# SD2IEC_TicTac.net
KiCad netlist of a schematic drawn in EAGLE
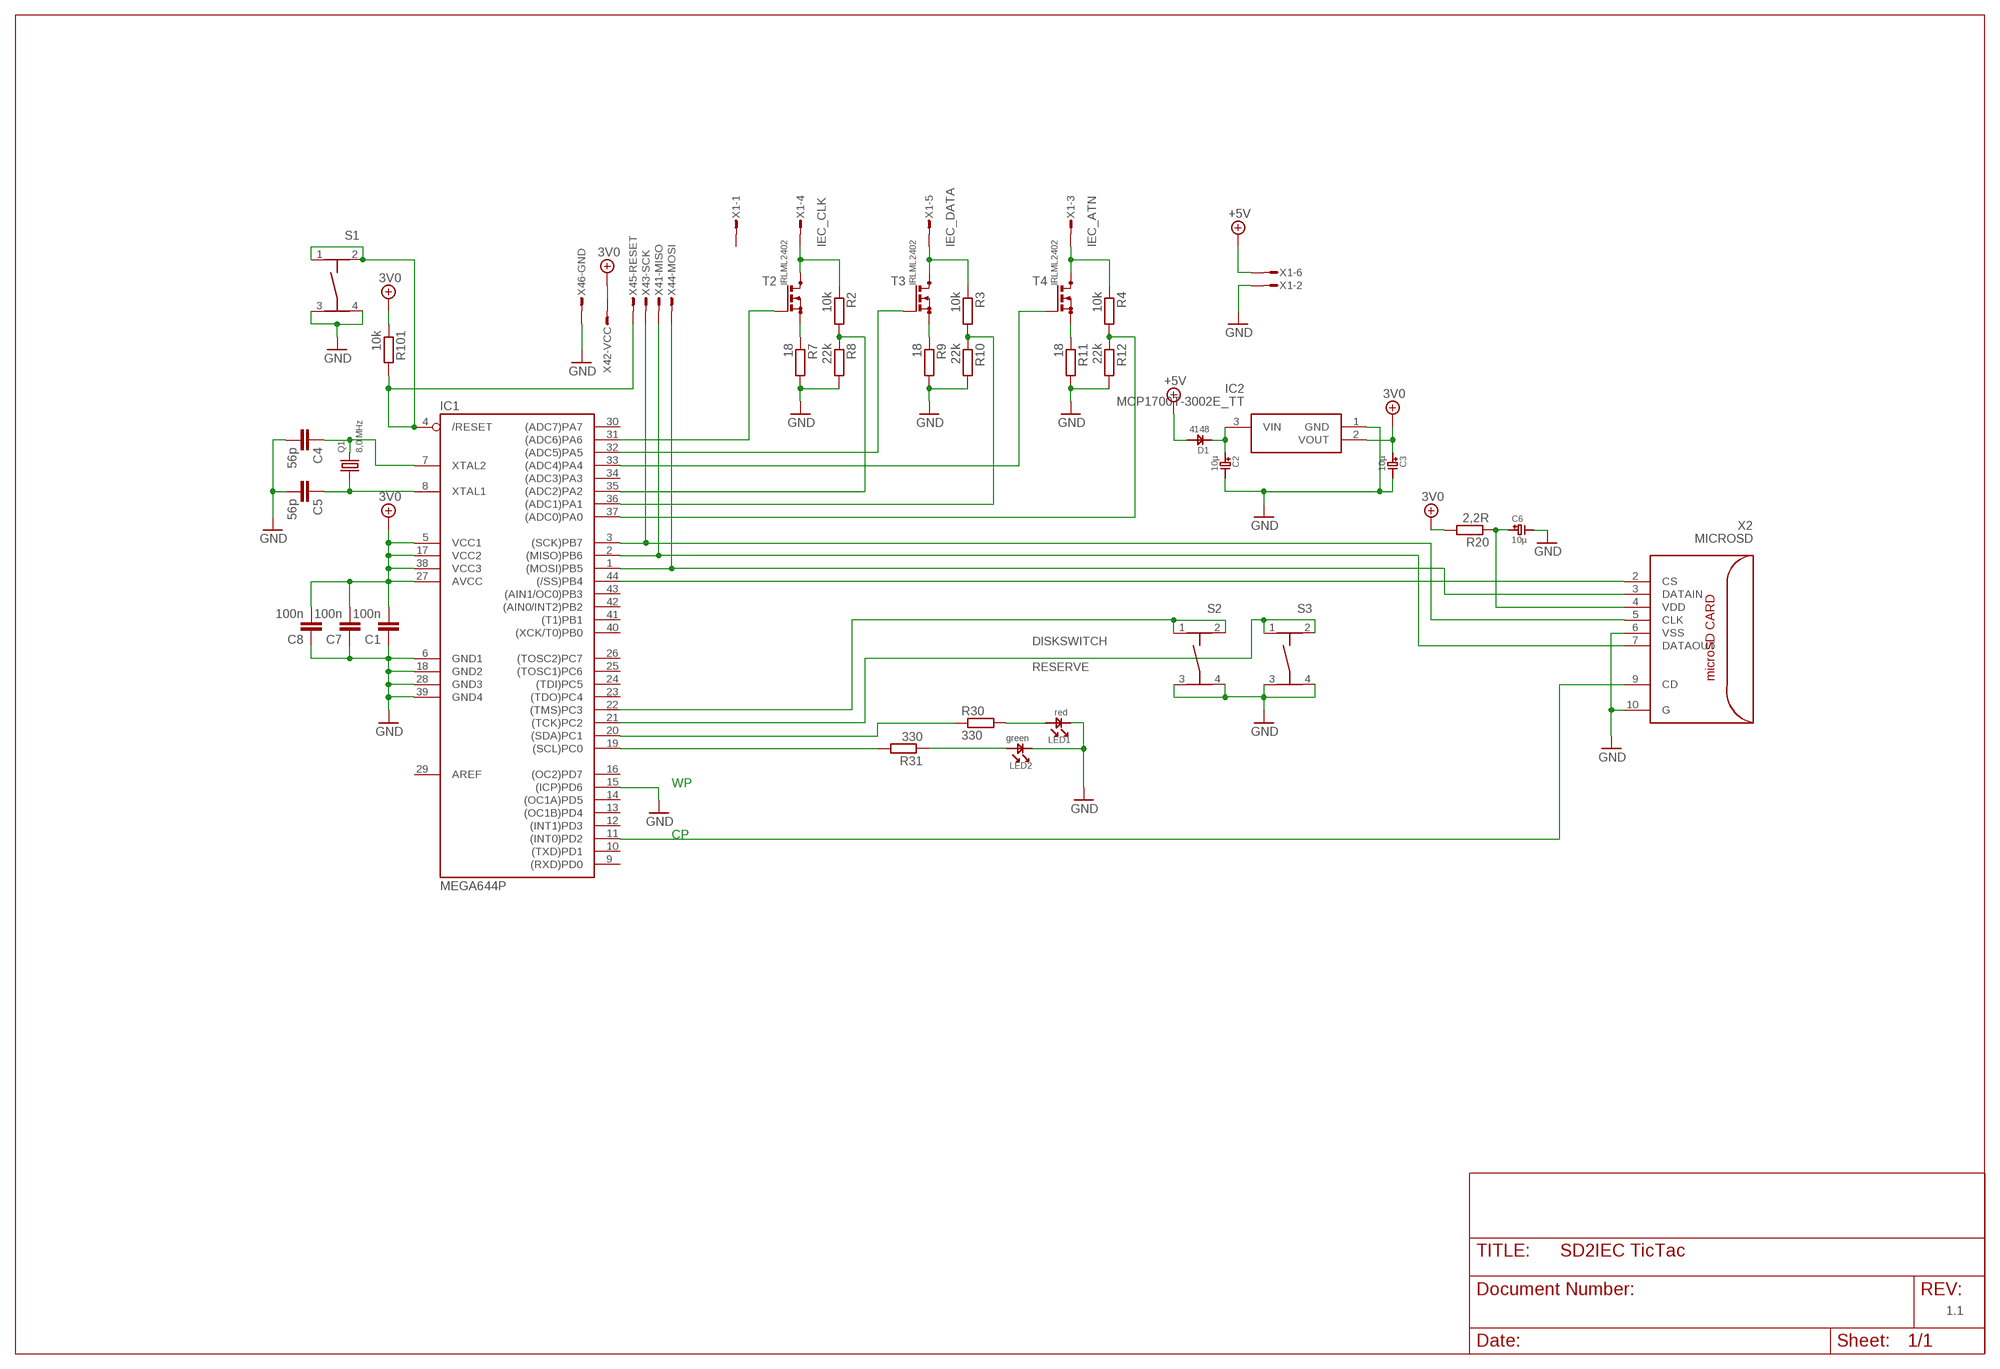
[diagram p0: schematic, sheet 1]

(export (version "E")
  (design (tool "Eeschema 10.0.6"))
  (components
    (comp (ref "C1")
      (value "100n")
      (footprint "eagle-import:C0805K")
      (libsource (lib "eagle-import") (part "C-EUC0805K"))
    )
    (comp (ref "C2")
      (value "10µ")
      (footprint "eagle-import:C_TANTAL_A")
      (libsource (lib "eagle-import") (part "C_POLTA_A"))
    )
    (comp (ref "C3")
      (value "10µ")
      (footprint "eagle-import:C_TANTAL_A")
      (libsource (lib "eagle-import") (part "C_POLTA_A"))
    )
    (comp (ref "C4")
      (value "56p")
      (footprint "eagle-import:C0805K")
      (libsource (lib "eagle-import") (part "C-EUC0805K"))
    )
    (comp (ref "C5")
      (value "56p")
      (footprint "eagle-import:C0805K")
      (libsource (lib "eagle-import") (part "C-EUC0805K"))
    )
    (comp (ref "C6")
      (value "10µ")
      (footprint "eagle-import:C_TANTAL_A")
      (libsource (lib "eagle-import") (part "C_POLTA_A"))
    )
    (comp (ref "C7")
      (value "100n")
      (footprint "eagle-import:C0805K")
      (libsource (lib "eagle-import") (part "C-EUC0805K"))
    )
    (comp (ref "C8")
      (value "100n")
      (footprint "eagle-import:C0805K")
      (libsource (lib "eagle-import") (part "C-EUC0805K"))
    )
    (comp (ref "D1")
      (value "4148")
      (footprint "eagle-import:SOD-123")
      (libsource (lib "eagle-import") (part "DSOD-123"))
    )
    (comp (ref "IC1")
      (value "MEGA644P")
      (footprint "eagle-import:TQFP44")
      (libsource (lib "eagle-import") (part "MEGA16/32TQFP"))
    )
    (comp (ref "IC2")
      (value "MCP1700T-3002E_TT")
      (footprint "eagle-import:SOT95P237X112-3N")
      (fields
        (field (name "MANUFACTURER_PART_NUMBER") "MCP1700T-3002E/TT")
        (field (name "RS_PART_NUMBER") "6989063P")
      )
      (libsource (lib "eagle-import") (part "MCP1700T-3002E_TT"))
    )
    (comp (ref "LED1")
      (value "red")
      (footprint "eagle-import:LED1206")
      (libsource (lib "eagle-import") (part "LED1206"))
    )
    (comp (ref "LED2")
      (value "green")
      (footprint "eagle-import:LED1206")
      (libsource (lib "eagle-import") (part "LED1206"))
    )
    (comp (ref "Q1")
      (value "8,0 MHz")
      (footprint "eagle-import:HC49_S")
      (libsource (lib "eagle-import") (part "HC49"))
    )
    (comp (ref "R2")
      (value "10k")
      (footprint "eagle-import:R0805")
      (libsource (lib "eagle-import") (part "R-EU_R0805"))
    )
    (comp (ref "R3")
      (value "10k")
      (footprint "eagle-import:R0805")
      (libsource (lib "eagle-import") (part "R-EU_R0805"))
    )
    (comp (ref "R4")
      (value "10k")
      (footprint "eagle-import:R0805")
      (libsource (lib "eagle-import") (part "R-EU_R0805"))
    )
    (comp (ref "R7")
      (value "18")
      (footprint "eagle-import:R0805")
      (libsource (lib "eagle-import") (part "R-EU_R0805"))
    )
    (comp (ref "R8")
      (value "22k")
      (footprint "eagle-import:R0805")
      (libsource (lib "eagle-import") (part "R-EU_R0805"))
    )
    (comp (ref "R9")
      (value "18")
      (footprint "eagle-import:R0805")
      (libsource (lib "eagle-import") (part "R-EU_R0805"))
    )
    (comp (ref "R10")
      (value "22k")
      (footprint "eagle-import:R0805")
      (libsource (lib "eagle-import") (part "R-EU_R0805"))
    )
    (comp (ref "R11")
      (value "18")
      (footprint "eagle-import:R0805")
      (libsource (lib "eagle-import") (part "R-EU_R0805"))
    )
    (comp (ref "R12")
      (value "22k")
      (footprint "eagle-import:R0805")
      (libsource (lib "eagle-import") (part "R-EU_R0805"))
    )
    (comp (ref "R20")
      (value "2,2R")
      (footprint "eagle-import:R0805")
      (libsource (lib "eagle-import") (part "R-EU_R0805"))
    )
    (comp (ref "R30")
      (value "330")
      (footprint "eagle-import:R0805")
      (libsource (lib "eagle-import") (part "R-EU_R0805"))
    )
    (comp (ref "R31")
      (value "330")
      (footprint "eagle-import:R0805")
      (libsource (lib "eagle-import") (part "R-EU_R0805"))
    )
    (comp (ref "R101")
      (value "10k")
      (footprint "eagle-import:R0805")
      (libsource (lib "eagle-import") (part "R-EU_R0805"))
    )
    (comp (ref "S1")
      (value "TASTER-9314_SMD")
      (footprint "eagle-import:TASTER-9314_SMD")
      (libsource (lib "eagle-import") (part "TASTER-9314_SMD"))
    )
    (comp (ref "S2")
      (value "TASTER-9314_SMD")
      (footprint "eagle-import:TASTER-9314_SMD")
      (libsource (lib "eagle-import") (part "TASTER-9314_SMD"))
    )
    (comp (ref "S3")
      (value "TASTER-9314_SMD")
      (footprint "eagle-import:TASTER-9314_SMD")
      (libsource (lib "eagle-import") (part "TASTER-9314_SMD"))
    )
    (comp (ref "T2")
      (value "IRLML2402")
      (footprint "eagle-import:SOT23_C")
      (libsource (lib "eagle-import") (part "BSN20_C"))
    )
    (comp (ref "T3")
      (value "IRLML2402")
      (footprint "eagle-import:SOT23_C")
      (libsource (lib "eagle-import") (part "BSN20_C"))
    )
    (comp (ref "T4")
      (value "IRLML2402")
      (footprint "eagle-import:SOT23_C")
      (libsource (lib "eagle-import") (part "BSN20_C"))
    )
    (comp (ref "X1")
      (value "MICROMATCH-6_PIN")
      (footprint "eagle-import:MICROMATCH-6")
      (libsource (lib "eagle-import") (part "MICROMATCH-6_PIN"))
    )
    (comp (ref "X2")
      (value "MICROSD")
      (footprint "eagle-import:MICRO_SD_CONNECTOR")
      (libsource (lib "eagle-import") (part "MICROSD_CHINA_SPI_MODE"))
    )
    (comp (ref "X4")
      (value "AVR-ISP_1X6")
      (footprint "eagle-import:1X6_ISP")
      (libsource (lib "eagle-import") (part "AVR-ISP_1X6"))
    )
  )
  (nets
    (net (code "1") (name "+5V") (class "Default")
      (node (ref "D1") (pin "2") (pinfunction "2_2") (pintype "passive"))
      (node (ref "X1") (pin "6") (pinfunction "S_6") (pintype "passive"))
    )
    (net (code "2") (name "/DISKSWITCH") (class "Default")
      (node (ref "IC1") (pin "22") (pinfunction "(TMS)PC3_22") (pintype "bidirectional"))
      (node (ref "S2") (pin "1") (pinfunction "1_1") (pintype "passive"))
      (node (ref "S2") (pin "2") (pinfunction "2_2") (pintype "passive"))
    )
    (net (code "3") (name "/IEC_ATN") (class "Default")
      (node (ref "R4") (pin "1") (pinfunction "1_1") (pintype "passive"))
      (node (ref "T4") (pin "3") (pinfunction "D_3") (pintype "passive"))
      (node (ref "X1") (pin "3") (pinfunction "S_3") (pintype "passive"))
    )
    (net (code "4") (name "/IEC_CLK") (class "Default")
      (node (ref "R2") (pin "1") (pinfunction "1_1") (pintype "passive"))
      (node (ref "T2") (pin "3") (pinfunction "D_3") (pintype "passive"))
      (node (ref "X1") (pin "4") (pinfunction "S_4") (pintype "passive"))
    )
    (net (code "5") (name "/IEC_DATA") (class "Default")
      (node (ref "R3") (pin "1") (pinfunction "1_1") (pintype "passive"))
      (node (ref "T3") (pin "3") (pinfunction "D_3") (pintype "passive"))
      (node (ref "X1") (pin "5") (pinfunction "S_5") (pintype "passive"))
    )
    (net (code "6") (name "/RESERVE") (class "Default")
      (node (ref "IC1") (pin "21") (pinfunction "(TCK)PC2_21") (pintype "bidirectional"))
      (node (ref "S3") (pin "1") (pinfunction "1_1") (pintype "passive"))
      (node (ref "S3") (pin "2") (pinfunction "2_2") (pintype "passive"))
    )
    (net (code "7") (name "3V0") (class "Default")
      (node (ref "C1") (pin "2") (pinfunction "2_2") (pintype "passive"))
      (node (ref "C3") (pin "1") (pinfunction "1_1") (pintype "passive"))
      (node (ref "C7") (pin "2") (pinfunction "2_2") (pintype "passive"))
      (node (ref "C8") (pin "2") (pinfunction "2_2") (pintype "passive"))
      (node (ref "IC1") (pin "17") (pinfunction "VCC2_17") (pintype "power_in"))
      (node (ref "IC1") (pin "27") (pinfunction "AVCC_27") (pintype "power_in"))
      (node (ref "IC1") (pin "38") (pinfunction "VCC3_38") (pintype "power_in"))
      (node (ref "IC1") (pin "5") (pinfunction "VCC1_5") (pintype "power_in"))
      (node (ref "IC2") (pin "2") (pinfunction "VOUT_2") (pintype "input"))
      (node (ref "R101") (pin "1") (pinfunction "1_1") (pintype "passive"))
      (node (ref "R20") (pin "2") (pinfunction "2_2") (pintype "passive"))
      (node (ref "X4") (pin "2") (pinfunction "S_2") (pintype "passive"))
    )
    (net (code "8") (name "GND") (class "Default")
      (node (ref "C1") (pin "1") (pinfunction "1_1") (pintype "passive"))
      (node (ref "C2") (pin "2") (pinfunction "2_2") (pintype "passive"))
      (node (ref "C3") (pin "2") (pinfunction "2_2") (pintype "passive"))
      (node (ref "C4") (pin "2") (pinfunction "2_2") (pintype "passive"))
      (node (ref "C5") (pin "2") (pinfunction "2_2") (pintype "passive"))
      (node (ref "C6") (pin "2") (pinfunction "2_2") (pintype "passive"))
      (node (ref "C7") (pin "1") (pinfunction "1_1") (pintype "passive"))
      (node (ref "C8") (pin "1") (pinfunction "1_1") (pintype "passive"))
      (node (ref "IC1") (pin "15") (pinfunction "(ICP)PD6_15") (pintype "bidirectional"))
      (node (ref "IC1") (pin "18") (pinfunction "GND2_18") (pintype "power_in"))
      (node (ref "IC1") (pin "28") (pinfunction "GND3_28") (pintype "power_in"))
      (node (ref "IC1") (pin "39") (pinfunction "GND4_39") (pintype "power_in"))
      (node (ref "IC1") (pin "6") (pinfunction "GND1_6") (pintype "power_in"))
      (node (ref "IC2") (pin "1") (pinfunction "GND_1") (pintype "input"))
      (node (ref "LED1") (pin "1") (pinfunction "1_1") (pintype "passive"))
      (node (ref "LED2") (pin "1") (pinfunction "1_1") (pintype "passive"))
      (node (ref "R10") (pin "2") (pinfunction "2_2") (pintype "passive"))
      (node (ref "R11") (pin "2") (pinfunction "2_2") (pintype "passive"))
      (node (ref "R12") (pin "2") (pinfunction "2_2") (pintype "passive"))
      (node (ref "R7") (pin "2") (pinfunction "2_2") (pintype "passive"))
      (node (ref "R8") (pin "2") (pinfunction "2_2") (pintype "passive"))
      (node (ref "R9") (pin "2") (pinfunction "2_2") (pintype "passive"))
      (node (ref "S1") (pin "3") (pinfunction "3_3") (pintype "passive"))
      (node (ref "S1") (pin "4") (pinfunction "4_4") (pintype "passive"))
      (node (ref "S2") (pin "3") (pinfunction "3_3") (pintype "passive"))
      (node (ref "S2") (pin "4") (pinfunction "4_4") (pintype "passive"))
      (node (ref "S3") (pin "3") (pinfunction "3_3") (pintype "passive"))
      (node (ref "S3") (pin "4") (pinfunction "4_4") (pintype "passive"))
      (node (ref "X1") (pin "2") (pinfunction "S_2") (pintype "passive"))
      (node (ref "X2") (pin "10") (pinfunction "G_10") (pintype "bidirectional"))
      (node (ref "X2") (pin "6") (pinfunction "VSS_6") (pintype "bidirectional"))
      (node (ref "X4") (pin "6") (pinfunction "S_6") (pintype "passive"))
    )
    (net (code "9") (name "Net-(IC1-(ADC0)PA0)") (class "Default")
      (node (ref "IC1") (pin "37") (pinfunction "(ADC0)PA0_37") (pintype "bidirectional"))
      (node (ref "R12") (pin "1") (pinfunction "1_1") (pintype "passive"))
      (node (ref "R4") (pin "2") (pinfunction "2_2") (pintype "passive"))
    )
    (net (code "10") (name "Net-(IC1-(ADC1)PA1)") (class "Default")
      (node (ref "IC1") (pin "36") (pinfunction "(ADC1)PA1_36") (pintype "bidirectional"))
      (node (ref "R10") (pin "1") (pinfunction "1_1") (pintype "passive"))
      (node (ref "R3") (pin "2") (pinfunction "2_2") (pintype "passive"))
    )
    (net (code "11") (name "Net-(IC1-(ADC2)PA2)") (class "Default")
      (node (ref "IC1") (pin "35") (pinfunction "(ADC2)PA2_35") (pintype "bidirectional"))
      (node (ref "R2") (pin "2") (pinfunction "2_2") (pintype "passive"))
      (node (ref "R8") (pin "1") (pinfunction "1_1") (pintype "passive"))
    )
    (net (code "12") (name "Net-(IC1-(ADC4)PA4)") (class "Default")
      (node (ref "IC1") (pin "33") (pinfunction "(ADC4)PA4_33") (pintype "bidirectional"))
      (node (ref "T4") (pin "1") (pinfunction "G_1") (pintype "passive"))
    )
    (net (code "13") (name "Net-(IC1-(ADC5)PA5)") (class "Default")
      (node (ref "IC1") (pin "32") (pinfunction "(ADC5)PA5_32") (pintype "bidirectional"))
      (node (ref "T3") (pin "1") (pinfunction "G_1") (pintype "passive"))
    )
    (net (code "14") (name "Net-(IC1-(ADC6)PA6)") (class "Default")
      (node (ref "IC1") (pin "31") (pinfunction "(ADC6)PA6_31") (pintype "bidirectional"))
      (node (ref "T2") (pin "1") (pinfunction "G_1") (pintype "passive"))
    )
    (net (code "15") (name "Net-(IC1-(INT0)PD2)") (class "Default")
      (node (ref "IC1") (pin "11") (pinfunction "(INT0)PD2_11") (pintype "bidirectional"))
      (node (ref "X2") (pin "9") (pinfunction "CD_9") (pintype "bidirectional"))
    )
    (net (code "16") (name "Net-(IC1-(MISO)PB6)") (class "Default")
      (node (ref "IC1") (pin "2") (pinfunction "(MISO)PB6_2") (pintype "bidirectional"))
      (node (ref "X2") (pin "7") (pinfunction "DATAOUT_7") (pintype "bidirectional"))
      (node (ref "X4") (pin "1") (pinfunction "S_1") (pintype "passive"))
    )
    (net (code "17") (name "Net-(IC1-(MOSI)PB5)") (class "Default")
      (node (ref "IC1") (pin "1") (pinfunction "(MOSI)PB5_1") (pintype "bidirectional"))
      (node (ref "X2") (pin "3") (pinfunction "DATAIN_3") (pintype "bidirectional"))
      (node (ref "X4") (pin "4") (pinfunction "S_4") (pintype "passive"))
    )
    (net (code "18") (name "Net-(IC1-(SCK)PB7)") (class "Default")
      (node (ref "IC1") (pin "3") (pinfunction "(SCK)PB7_3") (pintype "bidirectional"))
      (node (ref "X2") (pin "5") (pinfunction "CLK_5") (pintype "bidirectional"))
      (node (ref "X4") (pin "3") (pinfunction "S_3") (pintype "passive"))
    )
    (net (code "19") (name "Net-(IC1-(SCL)PC0)") (class "Default")
      (node (ref "IC1") (pin "19") (pinfunction "(SCL)PC0_19") (pintype "bidirectional"))
      (node (ref "R31") (pin "2") (pinfunction "2_2") (pintype "passive"))
    )
    (net (code "20") (name "Net-(IC1-(SDA)PC1)") (class "Default")
      (node (ref "IC1") (pin "20") (pinfunction "(SDA)PC1_20") (pintype "bidirectional"))
      (node (ref "R30") (pin "1") (pinfunction "1_1") (pintype "passive"))
    )
    (net (code "21") (name "Net-(IC1-({slash}SS)PB4)") (class "Default")
      (node (ref "IC1") (pin "44") (pinfunction "(/SS)PB4_44") (pintype "bidirectional"))
      (node (ref "X2") (pin "2") (pinfunction "CS_2") (pintype "bidirectional"))
    )
    (net (code "22") (name "Net-(IC1-XTAL1)") (class "Default")
      (node (ref "C5") (pin "1") (pinfunction "1_1") (pintype "passive"))
      (node (ref "IC1") (pin "8") (pinfunction "XTAL1_8") (pintype "input"))
      (node (ref "Q1") (pin "1") (pinfunction "1_1") (pintype "passive"))
    )
    (net (code "23") (name "Net-(IC1-XTAL2)") (class "Default")
      (node (ref "C4") (pin "1") (pinfunction "1_1") (pintype "passive"))
      (node (ref "IC1") (pin "7") (pinfunction "XTAL2_7") (pintype "input"))
      (node (ref "Q1") (pin "2") (pinfunction "2_2") (pintype "passive"))
    )
    (net (code "24") (name "Net-(IC1-{slash}RESET)") (class "Default")
      (node (ref "IC1") (pin "4") (pinfunction "/RESET_4") (pintype "input"))
      (node (ref "R101") (pin "2") (pinfunction "2_2") (pintype "passive"))
      (node (ref "S1") (pin "1") (pinfunction "1_1") (pintype "passive"))
      (node (ref "S1") (pin "2") (pinfunction "2_2") (pintype "passive"))
      (node (ref "X4") (pin "5") (pinfunction "S_5") (pintype "passive"))
    )
    (net (code "25") (name "Net-(IC2-VIN)") (class "Default")
      (node (ref "C2") (pin "1") (pinfunction "1_1") (pintype "passive"))
      (node (ref "D1") (pin "1") (pinfunction "1_1") (pintype "passive"))
      (node (ref "IC2") (pin "3") (pinfunction "VIN_3") (pintype "input"))
    )
    (net (code "26") (name "Net-(LED1-Pad2)") (class "Default")
      (node (ref "LED1") (pin "2") (pinfunction "2_2") (pintype "passive"))
      (node (ref "R30") (pin "2") (pinfunction "2_2") (pintype "passive"))
    )
    (net (code "27") (name "Net-(LED2-Pad2)") (class "Default")
      (node (ref "LED2") (pin "2") (pinfunction "2_2") (pintype "passive"))
      (node (ref "R31") (pin "1") (pinfunction "1_1") (pintype "passive"))
    )
    (net (code "28") (name "Net-(T2-S)") (class "Default")
      (node (ref "R7") (pin "1") (pinfunction "1_1") (pintype "passive"))
      (node (ref "T2") (pin "2") (pinfunction "S_2") (pintype "passive"))
    )
    (net (code "29") (name "Net-(T3-S)") (class "Default")
      (node (ref "R9") (pin "1") (pinfunction "1_1") (pintype "passive"))
      (node (ref "T3") (pin "2") (pinfunction "S_2") (pintype "passive"))
    )
    (net (code "30") (name "Net-(T4-S)") (class "Default")
      (node (ref "R11") (pin "1") (pinfunction "1_1") (pintype "passive"))
      (node (ref "T4") (pin "2") (pinfunction "S_2") (pintype "passive"))
    )
    (net (code "31") (name "Net-(X2-VDD)") (class "Default")
      (node (ref "C6") (pin "1") (pinfunction "1_1") (pintype "passive"))
      (node (ref "R20") (pin "1") (pinfunction "1_1") (pintype "passive"))
      (node (ref "X2") (pin "4") (pinfunction "VDD_4") (pintype "bidirectional"))
    )
    (net (code "32") (name "unconnected-(IC1-(ADC3)PA3-Pad34)") (class "Default")
      (node (ref "IC1") (pin "34") (pinfunction "(ADC3)PA3_34") (pintype "bidirectional"))
    )
    (net (code "33") (name "unconnected-(IC1-(ADC7)PA7-Pad30)") (class "Default")
      (node (ref "IC1") (pin "30") (pinfunction "(ADC7)PA7_30") (pintype "bidirectional"))
    )
    (net (code "34") (name "unconnected-(IC1-(AIN0{slash}INT2)PB2-Pad42)") (class "Default")
      (node (ref "IC1") (pin "42") (pinfunction "(AIN0/INT2)PB2_42") (pintype "bidirectional"))
    )
    (net (code "35") (name "unconnected-(IC1-(AIN1{slash}OC0)PB3-Pad43)") (class "Default")
      (node (ref "IC1") (pin "43") (pinfunction "(AIN1/OC0)PB3_43") (pintype "bidirectional"))
    )
    (net (code "36") (name "unconnected-(IC1-(INT1)PD3-Pad12)") (class "Default")
      (node (ref "IC1") (pin "12") (pinfunction "(INT1)PD3_12") (pintype "bidirectional"))
    )
    (net (code "37") (name "unconnected-(IC1-(OC1A)PD5-Pad14)") (class "Default")
      (node (ref "IC1") (pin "14") (pinfunction "(OC1A)PD5_14") (pintype "bidirectional"))
    )
    (net (code "38") (name "unconnected-(IC1-(OC1B)PD4-Pad13)") (class "Default")
      (node (ref "IC1") (pin "13") (pinfunction "(OC1B)PD4_13") (pintype "bidirectional"))
    )
    (net (code "39") (name "unconnected-(IC1-(OC2)PD7-Pad16)") (class "Default")
      (node (ref "IC1") (pin "16") (pinfunction "(OC2)PD7_16") (pintype "bidirectional"))
    )
    (net (code "40") (name "unconnected-(IC1-(RXD)PD0-Pad9)") (class "Default")
      (node (ref "IC1") (pin "9") (pinfunction "(RXD)PD0_9") (pintype "bidirectional"))
    )
    (net (code "41") (name "unconnected-(IC1-(T1)PB1-Pad41)") (class "Default")
      (node (ref "IC1") (pin "41") (pinfunction "(T1)PB1_41") (pintype "bidirectional"))
    )
    (net (code "42") (name "unconnected-(IC1-(TDI)PC5-Pad24)") (class "Default")
      (node (ref "IC1") (pin "24") (pinfunction "(TDI)PC5_24") (pintype "bidirectional"))
    )
    (net (code "43") (name "unconnected-(IC1-(TDO)PC4-Pad23)") (class "Default")
      (node (ref "IC1") (pin "23") (pinfunction "(TDO)PC4_23") (pintype "bidirectional"))
    )
    (net (code "44") (name "unconnected-(IC1-(TOSC1)PC6-Pad25)") (class "Default")
      (node (ref "IC1") (pin "25") (pinfunction "(TOSC1)PC6_25") (pintype "bidirectional"))
    )
    (net (code "45") (name "unconnected-(IC1-(TOSC2)PC7-Pad26)") (class "Default")
      (node (ref "IC1") (pin "26") (pinfunction "(TOSC2)PC7_26") (pintype "bidirectional"))
    )
    (net (code "46") (name "unconnected-(IC1-(TXD)PD1-Pad10)") (class "Default")
      (node (ref "IC1") (pin "10") (pinfunction "(TXD)PD1_10") (pintype "bidirectional"))
    )
    (net (code "47") (name "unconnected-(IC1-(XCK{slash}T0)PB0-Pad40)") (class "Default")
      (node (ref "IC1") (pin "40") (pinfunction "(XCK/T0)PB0_40") (pintype "bidirectional"))
    )
    (net (code "48") (name "unconnected-(IC1-AREF-Pad29)") (class "Default")
      (node (ref "IC1") (pin "29") (pinfunction "AREF_29") (pintype "bidirectional"))
    )
    (net (code "49") (name "unconnected-(X1A-S-Pad1)") (class "Default")
      (node (ref "X1") (pin "1") (pinfunction "S_1") (pintype "passive"))
    )
  )
)
